# demoV1_0.net
KiCad netlist of a schematic drawn in Altium Designer
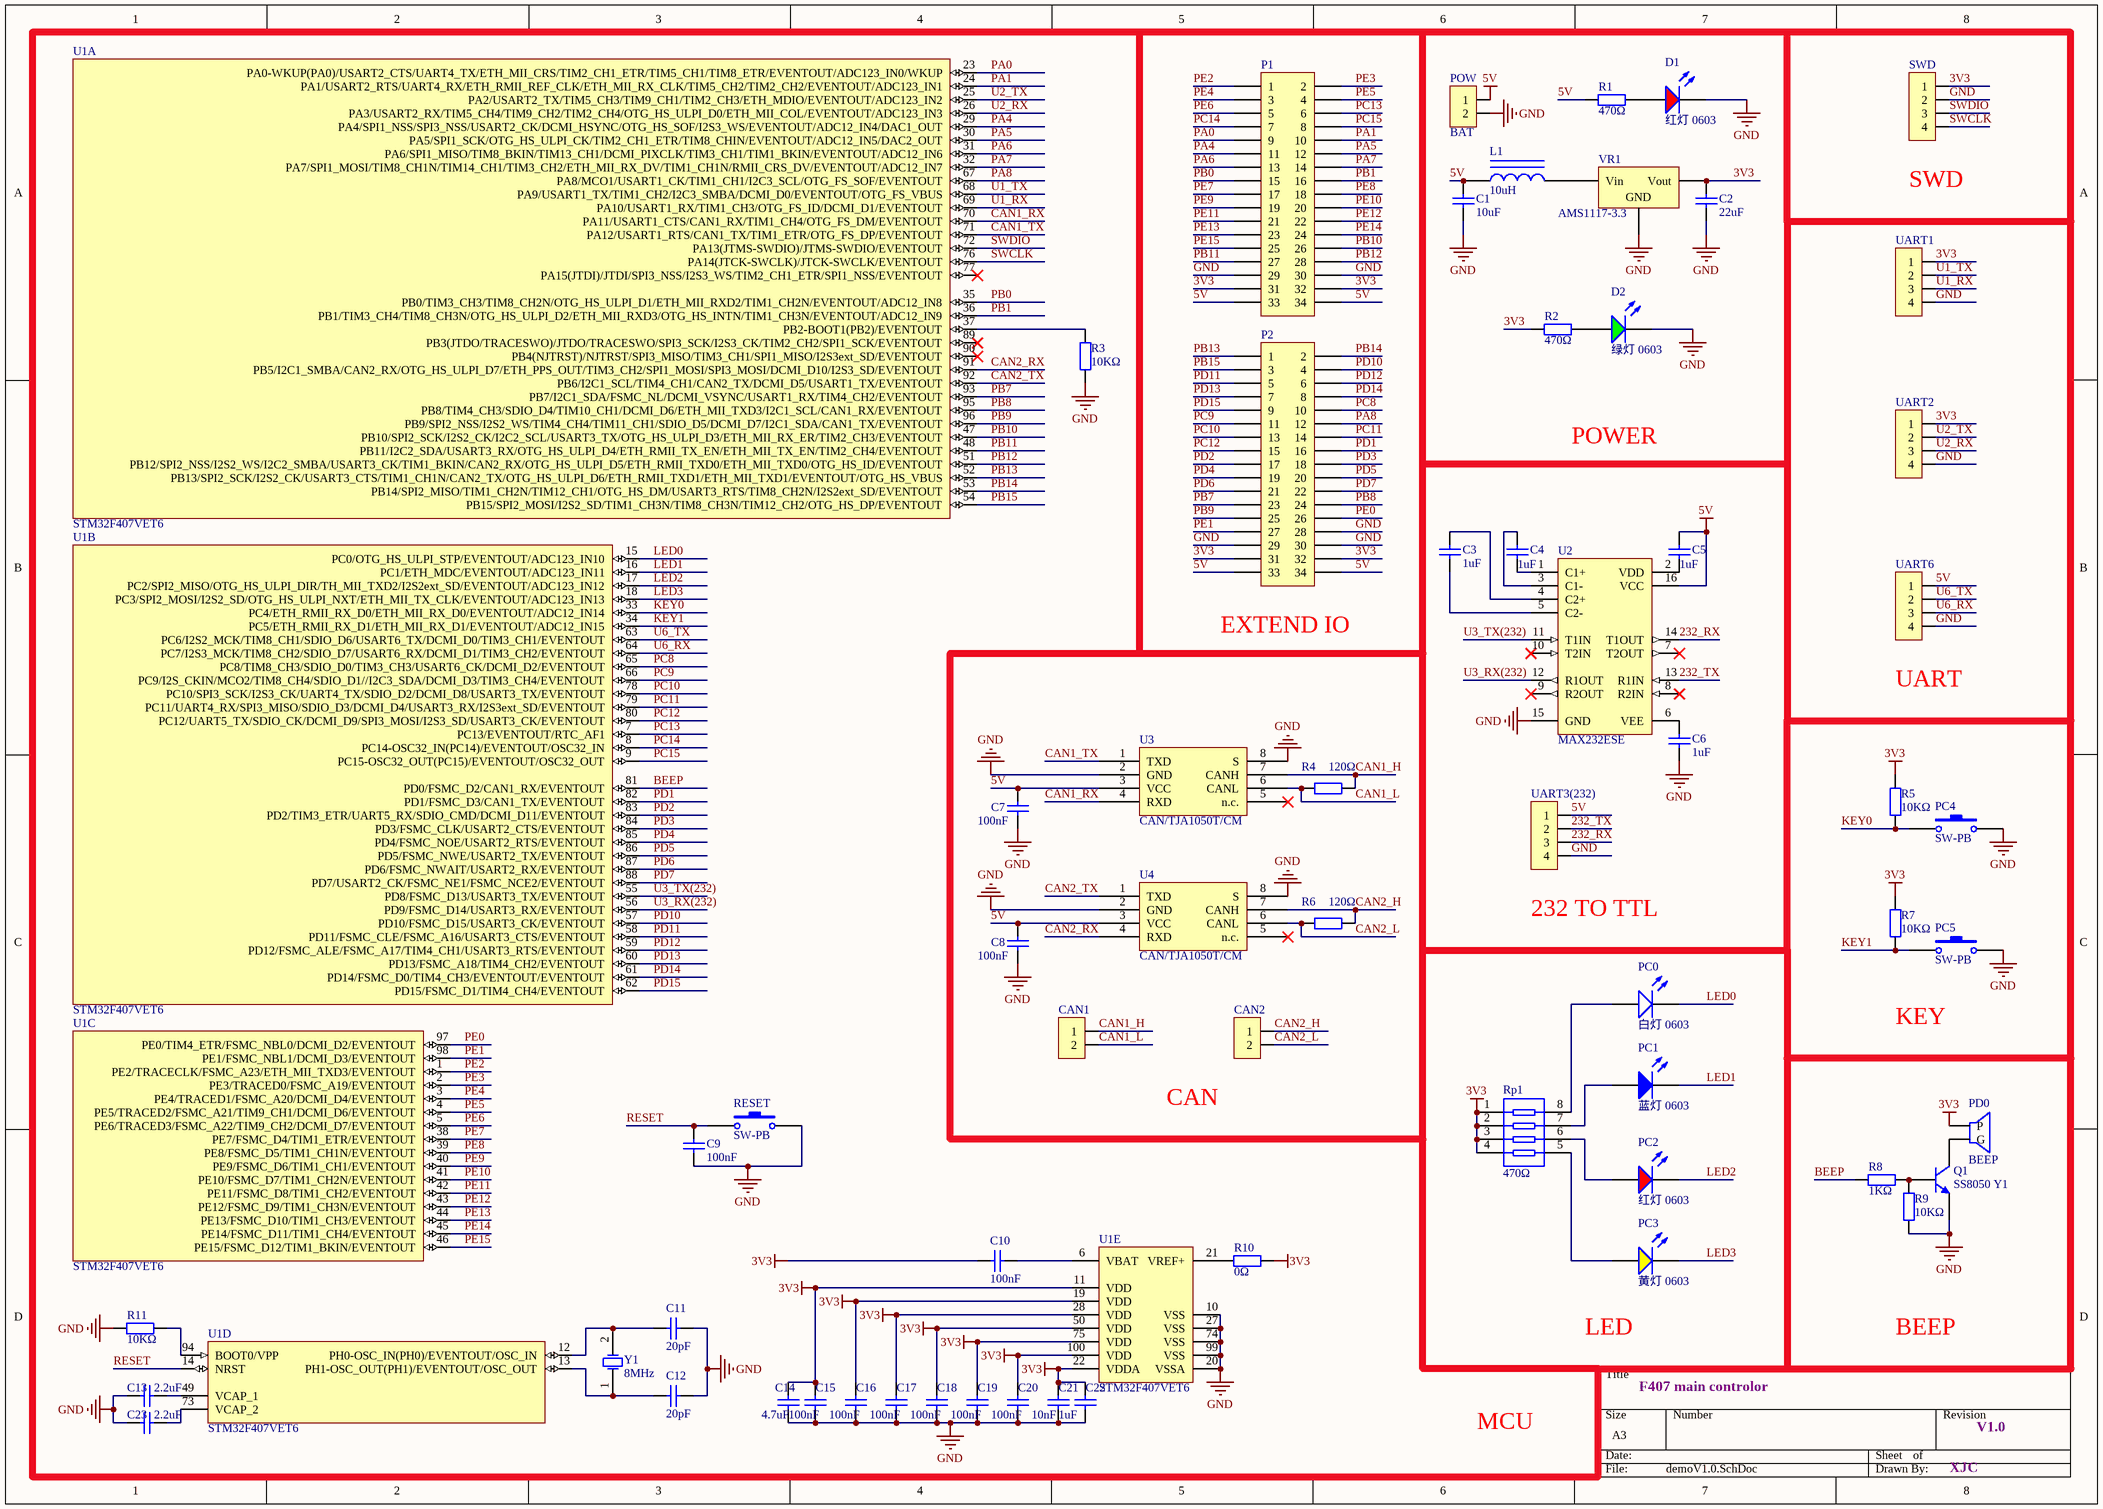
[diagram p0: demoV1.0.SchDoc]

(export (version "E")
  (design (tool "Eeschema 10.0.6"))
  (components
    (comp (ref "C1")
      (value "10uF")
      (footprint "0603_C")
      (description "贴片电容")
      (libsource (lib "Cap") (part "0603 10uF (106) 10% 10V"))
    )
    (comp (ref "C2")
      (value "22uF")
      (footprint "0603_C")
      (description "贴片电容")
      (libsource (lib "Cap") (part "0603 22uF (226) 20% 6.3V"))
    )
    (comp (ref "C3")
      (value "1uF")
      (footprint "0603_C")
      (description "贴片电容")
      (libsource (lib "Cap") (part "0603 1uF (105) 10% 50V"))
    )
    (comp (ref "C4")
      (value "1uF")
      (footprint "0603_C")
      (description "贴片电容")
      (libsource (lib "Cap") (part "0603 1uF (105) 10% 50V"))
    )
    (comp (ref "C5")
      (value "1uF")
      (footprint "0603_C")
      (description "贴片电容")
      (libsource (lib "Cap") (part "0603 1uF (105) 10% 50V"))
    )
    (comp (ref "C6")
      (value "1uF")
      (footprint "0603_C")
      (description "贴片电容")
      (libsource (lib "Cap") (part "0603 1uF (105) 10% 50V"))
    )
    (comp (ref "C7")
      (value "100nF")
      (footprint "0603_C")
      (description "贴片电容")
      (libsource (lib "Cap") (part "0603 100nF (104) 10% 50V"))
    )
    (comp (ref "C8")
      (value "100nF")
      (footprint "0603_C")
      (description "贴片电容")
      (libsource (lib "Cap") (part "0603 100nF (104) 10% 50V"))
    )
    (comp (ref "C9")
      (value "100nF")
      (footprint "0603_C")
      (description "贴片电容")
      (libsource (lib "Cap") (part "0603 100nF (104) 10% 50V"))
    )
    (comp (ref "C10")
      (value "100nF")
      (footprint "0603_C")
      (description "贴片电容")
      (libsource (lib "Cap") (part "0603 100nF (104) 10% 50V"))
    )
    (comp (ref "C11")
      (value "20pF")
      (footprint "0603_C")
      (description "贴片电容")
      (libsource (lib "Cap") (part "0603 20pF (200) 5% 50V"))
    )
    (comp (ref "C12")
      (value "20pF")
      (footprint "0603_C")
      (description "贴片电容")
      (libsource (lib "Cap") (part "0603 20pF (200) 5% 50V"))
    )
    (comp (ref "C13")
      (value "2.2uF")
      (footprint "0603_C")
      (description "贴片电容")
      (libsource (lib "Cap") (part "0603 2.2uF (225) 10% 16V"))
    )
    (comp (ref "C14")
      (value "4.7uF")
      (footprint "0603_C")
      (description "贴片电容")
      (libsource (lib "Cap") (part "0603 4.7uF (475) 10% 16V"))
    )
    (comp (ref "C15")
      (value "100nF")
      (footprint "0603_C")
      (description "贴片电容")
      (libsource (lib "Cap") (part "0603 100nF (104) 10% 50V"))
    )
    (comp (ref "C16")
      (value "100nF")
      (footprint "0603_C")
      (description "贴片电容")
      (libsource (lib "Cap") (part "0603 100nF (104) 10% 50V"))
    )
    (comp (ref "C17")
      (value "100nF")
      (footprint "0603_C")
      (description "贴片电容")
      (libsource (lib "Cap") (part "0603 100nF (104) 10% 50V"))
    )
    (comp (ref "C18")
      (value "100nF")
      (footprint "0603_C")
      (description "贴片电容")
      (libsource (lib "Cap") (part "0603 100nF (104) 10% 50V"))
    )
    (comp (ref "C19")
      (value "100nF")
      (footprint "0603_C")
      (description "贴片电容")
      (libsource (lib "Cap") (part "0603 100nF (104) 10% 50V"))
    )
    (comp (ref "C20")
      (value "100nF")
      (footprint "0603_C")
      (description "贴片电容")
      (libsource (lib "Cap") (part "0603 100nF (104) 10% 50V"))
    )
    (comp (ref "C21")
      (value "10nF")
      (footprint "0603_C")
      (description "贴片电容")
      (libsource (lib "Cap") (part "0603 10nF (103) 10% 50V"))
    )
    (comp (ref "C22")
      (value "1uF")
      (footprint "0603_C")
      (description "贴片电容")
      (libsource (lib "Cap") (part "0603 1uF (105) 10% 50V"))
    )
    (comp (ref "C23")
      (value "2.2uF")
      (footprint "0603_C")
      (description "贴片电容")
      (libsource (lib "Cap") (part "0603 2.2uF (225) 10% 16V"))
    )
    (comp (ref "CAN1")
      (value "CAN")
      (footprint "XH-2")
      (description "Connector")
      (libsource (lib "连接器件") (part "CON2"))
    )
    (comp (ref "CAN2")
      (value "CAN")
      (footprint "XH-2")
      (description "Connector")
      (libsource (lib "连接器件") (part "CON2"))
    )
    (comp (ref "D1")
      (value "红灯 0603")
      (footprint "0603_LED_S1")
      (description "发光二极管")
      (libsource (lib "LED") (part "0603 红灯"))
    )
    (comp (ref "D2")
      (value "绿灯 0603")
      (footprint "0603_LED_S1")
      (description "发光二极管")
      (libsource (lib "LED") (part "0603 绿灯"))
    )
    (comp (ref "L1")
      (value "10uH")
      (footprint "0603_L")
      (description "贴片电感")
      (libsource (lib "IUD") (part "0603 10uH 10%"))
    )
    (comp (ref "P1")
      (value "Header 17X2")
      (footprint "HDR2X17")
      (description "Header, 17-Pin, Dual row")
      (fields (field (name "PUBLISHER") "Altium Limited"))
      (libsource (lib "Miscellaneous Connectors") (part "Header 17X2"))
    )
    (comp (ref "P2")
      (value "Header 17X2")
      (footprint "HDR2X17")
      (description "Header, 17-Pin, Dual row")
      (fields (field (name "PUBLISHER") "Altium Limited"))
      (libsource (lib "Miscellaneous Connectors") (part "Header 17X2"))
    )
    (comp (ref "PC0")
      (value "白灯 0603")
      (footprint "0603_LED_S1")
      (description "发光二极管")
      (libsource (lib "LED") (part "0603 白灯"))
    )
    (comp (ref "PC1")
      (value "蓝灯 0603")
      (footprint "0603_LED_S1")
      (description "发光二极管")
      (libsource (lib "LED") (part "0603 蓝灯"))
    )
    (comp (ref "PC2")
      (value "红灯 0603")
      (footprint "0603_LED_S1")
      (description "发光二极管")
      (libsource (lib "LED") (part "0603 红灯"))
    )
    (comp (ref "PC3")
      (value "黄灯 0603")
      (footprint "0603_LED_S1")
      (description "发光二极管")
      (libsource (lib "LED") (part "0603 黄灯"))
    )
    (comp (ref "PC4")
      (value "SW-PB")
      (footprint "SW_PB2_A1")
      (description "微动开关")
      (fields (field (name "PUBLISHER") "Altium Limited"))
      (libsource (lib "Fszhang") (part "SW-PB"))
    )
    (comp (ref "PC5")
      (value "SW-PB")
      (footprint "SW_PB2_A1")
      (description "微动开关")
      (fields (field (name "PUBLISHER") "Altium Limited"))
      (libsource (lib "Fszhang") (part "SW-PB"))
    )
    (comp (ref "PD0")
      (value "BEEP")
      (footprint "BELL-5")
      (libsource (lib "Explorer STM32F407封装库") (part "BEEP"))
    )
    (comp (ref "POW")
      (value "BAT")
      (footprint "XH-2")
      (description "Connector")
      (libsource (lib "连接器件") (part "CON2"))
    )
    (comp (ref "Q1")
      (value "SS8050 Y1")
      (footprint "SOT-23(SOT-23-3)")
      (description "三极管")
      (libsource (lib "Transistor_NPN") (part "SOT-23 SS8050 Y1"))
    )
    (comp (ref "R1")
      (value "470Ω")
      (footprint "0603_R")
      (description "贴片电阻")
      (libsource (lib "RES") (part "0603 470Ω (4700) 1%"))
    )
    (comp (ref "R2")
      (value "470Ω")
      (footprint "0603_R")
      (description "贴片电阻")
      (libsource (lib "RES") (part "0603 470Ω (4700) 1%"))
    )
    (comp (ref "R3")
      (value "10KΩ")
      (footprint "0603_R")
      (description "贴片电阻")
      (libsource (lib "RES") (part "0603 10KΩ (1002) 1%"))
    )
    (comp (ref "R4")
      (value "120Ω")
      (footprint "0603_R")
      (description "贴片电阻")
      (libsource (lib "RES") (part "0603 120Ω (1200) 1%"))
    )
    (comp (ref "R5")
      (value "10KΩ")
      (footprint "0603_R")
      (description "贴片电阻")
      (libsource (lib "RES") (part "0603 10KΩ (1002) 1%"))
    )
    (comp (ref "R6")
      (value "120Ω")
      (footprint "0603_R")
      (description "贴片电阻")
      (libsource (lib "RES") (part "0603 120Ω (1200) 1%"))
    )
    (comp (ref "R7")
      (value "10KΩ")
      (footprint "0603_R")
      (description "贴片电阻")
      (libsource (lib "RES") (part "0603 10KΩ (1002) 1%"))
    )
    (comp (ref "R8")
      (value "1KΩ")
      (footprint "0603_R")
      (description "贴片电阻")
      (libsource (lib "RES") (part "0603 1KΩ (1001) 1%"))
    )
    (comp (ref "R9")
      (value "10KΩ")
      (footprint "0603_R")
      (description "贴片电阻")
      (libsource (lib "RES") (part "0603 10KΩ (1002) 1%"))
    )
    (comp (ref "R10")
      (value "0Ω")
      (footprint "0603_R")
      (description "贴片电阻")
      (libsource (lib "RES") (part "0603 0Ω (0R0) 1%"))
    )
    (comp (ref "R11")
      (value "10KΩ")
      (footprint "0603_R")
      (description "贴片电阻")
      (libsource (lib "") (part "0603 10KΩ (1002) 1%_1"))
    )
    (comp (ref "RESET")
      (value "SW-PB")
      (footprint "SW_PB2_A1")
      (description "微动开关")
      (fields (field (name "PUBLISHER") "Altium Limited"))
      (libsource (lib "Fszhang") (part "SW-PB"))
    )
    (comp (ref "Rp1")
      (value "470Ω")
      (footprint "0603_Rx4")
      (description "贴片排阻")
      (libsource (lib "RES") (part "0603*4 470Ω (471) 5%"))
    )
    (comp (ref "SWD")
      (value "SWD")
      (footprint "PH-4")
      (description "Connector")
      (libsource (lib "连接器件") (part "CON4"))
    )
    (comp (ref "U1")
      (value "STM32F407VET6")
      (footprint "LQFP-100_14x14x05P")
      (description "ARM")
      (libsource (lib "MCU") (part "STM32F407VET6"))
    )
    (comp (ref "U2")
      (value "MAX232ESE")
      (footprint "SOIC-16_150mil")
      (description "RS232")
      (libsource (lib "IC") (part "MAX232ESE_[C26860]"))
    )
    (comp (ref "U3")
      (value "CAN/TJA1050T/CM")
      (footprint "SOIC-8_150mil")
      (description "CAN")
      (libsource (lib "IC") (part "CAN/TJA1050T/CM_[C6952]"))
    )
    (comp (ref "U4")
      (value "CAN/TJA1050T/CM")
      (footprint "SOIC-8_150mil")
      (description "CAN")
      (libsource (lib "IC") (part "CAN/TJA1050T/CM_[C6952]"))
    )
    (comp (ref "UART1")
      (value "~")
      (footprint "XH-4")
      (description "Connector")
      (libsource (lib "连接器件") (part "CON4"))
    )
    (comp (ref "UART2")
      (value "~")
      (footprint "XH-4")
      (description "Connector")
      (libsource (lib "连接器件") (part "CON4"))
    )
    (comp (ref "UART3(232)")
      (value "~")
      (footprint "XH-4")
      (description "Connector")
      (libsource (lib "连接器件") (part "CON4"))
    )
    (comp (ref "UART6")
      (value "~")
      (footprint "XH-4")
      (description "Connector")
      (libsource (lib "连接器件") (part "CON4"))
    )
    (comp (ref "VR1")
      (value "AMS1117-3.3")
      (footprint "SOT-223")
      (description "低压差线性稳压(LDO)")
      (libsource (lib "LDO") (part "SOT-223 AMS1117-3.3"))
    )
    (comp (ref "Y1")
      (value "8MHz")
      (footprint "SMD-5032_2P")
      (description "贴片晶振")
      (libsource (lib "CrystalOscillator") (part "SMD-5032_2P 8MHz 20ppm 20pF"))
    )
  )
  (nets
    (net (code "1") (name "/232_RX") (class "Default")
      (node (ref "U2") (pin "14") (pinfunction "T1OUT_14") (pintype "output"))
      (node (ref "UART3(232)") (pin "3") (pinfunction "3_3") (pintype "passive"))
    )
    (net (code "2") (name "/232_TX") (class "Default")
      (node (ref "U2") (pin "13") (pinfunction "R1IN_13") (pintype "input"))
      (node (ref "UART3(232)") (pin "2") (pinfunction "2_2") (pintype "passive"))
    )
    (net (code "3") (name "/BEEP") (class "Default")
      (node (ref "R8") (pin "1") (pinfunction "1_1") (pintype "passive"))
      (node (ref "U1") (pin "81") (pinfunction "PD0/FSMC_D2/CAN1_RX/EVENTOUT_81") (pintype "bidirectional"))
    )
    (net (code "4") (name "/CAN1_H") (class "Default")
      (node (ref "CAN1") (pin "1") (pinfunction "1_1") (pintype "passive"))
      (node (ref "R4") (pin "2") (pinfunction "2_2") (pintype "passive"))
      (node (ref "U3") (pin "7") (pinfunction "CANH_7") (pintype "passive"))
    )
    (net (code "5") (name "/CAN1_L") (class "Default")
      (node (ref "CAN1") (pin "2") (pinfunction "2_2") (pintype "passive"))
      (node (ref "R4") (pin "1") (pinfunction "1_1") (pintype "passive"))
      (node (ref "U3") (pin "6") (pinfunction "CANL_6") (pintype "passive"))
    )
    (net (code "6") (name "/CAN1_RX") (class "Default")
      (node (ref "U1") (pin "70") (pinfunction "PA11/USART1_CTS/CAN1_RX/TIM1_CH4/OTG_FS_DM/EVENTOUT_70") (pintype "bidirectional"))
      (node (ref "U3") (pin "4") (pinfunction "RXD_4") (pintype "passive"))
    )
    (net (code "7") (name "/CAN1_TX") (class "Default")
      (node (ref "U1") (pin "71") (pinfunction "PA12/USART1_RTS/CAN1_TX/TIM1_ETR/OTG_FS_DP/EVENTOUT_71") (pintype "bidirectional"))
      (node (ref "U3") (pin "1") (pinfunction "TXD_1") (pintype "passive"))
    )
    (net (code "8") (name "/CAN2_H") (class "Default")
      (node (ref "CAN2") (pin "1") (pinfunction "1_1") (pintype "passive"))
      (node (ref "R6") (pin "2") (pinfunction "2_2") (pintype "passive"))
      (node (ref "U4") (pin "7") (pinfunction "CANH_7") (pintype "passive"))
    )
    (net (code "9") (name "/CAN2_L") (class "Default")
      (node (ref "CAN2") (pin "2") (pinfunction "2_2") (pintype "passive"))
      (node (ref "R6") (pin "1") (pinfunction "1_1") (pintype "passive"))
      (node (ref "U4") (pin "6") (pinfunction "CANL_6") (pintype "passive"))
    )
    (net (code "10") (name "/CAN2_RX") (class "Default")
      (node (ref "U1") (pin "91") (pinfunction "PB5/I2C1_SMBA/CAN2_RX/OTG_HS_ULPI_D7/ETH_PPS_OUT/TIM3_CH2/SPI1_MOSI/SPI3_MOSI/DCMI_D10/I2S3_SD/EVENTOUT_91") (pintype "bidirectional"))
      (node (ref "U4") (pin "4") (pinfunction "RXD_4") (pintype "passive"))
    )
    (net (code "11") (name "/CAN2_TX") (class "Default")
      (node (ref "U1") (pin "92") (pinfunction "PB6/I2C1_SCL/TIM4_CH1/CAN2_TX/DCMI_D5/USART1_TX/EVENTOUT_92") (pintype "bidirectional"))
      (node (ref "U4") (pin "1") (pinfunction "TXD_1") (pintype "passive"))
    )
    (net (code "12") (name "/KEY0") (class "Default")
      (node (ref "PC4") (pin "1") (pinfunction "1_1") (pintype "passive"))
      (node (ref "R5") (pin "1") (pinfunction "1_1") (pintype "passive"))
      (node (ref "U1") (pin "33") (pinfunction "PC4/ETH_RMII_RX_D0/ETH_MII_RX_D0/EVENTOUT/ADC12_IN14_33") (pintype "bidirectional"))
    )
    (net (code "13") (name "/KEY1") (class "Default")
      (node (ref "PC5") (pin "1") (pinfunction "1_1") (pintype "passive"))
      (node (ref "R7") (pin "1") (pinfunction "1_1") (pintype "passive"))
      (node (ref "U1") (pin "34") (pinfunction "PC5/ETH_RMII_RX_D1/ETH_MII_RX_D1/EVENTOUT/ADC12_IN15_34") (pintype "bidirectional"))
    )
    (net (code "14") (name "/LED0") (class "Default")
      (node (ref "PC0") (pin "K") (pinfunction "K_K") (pintype "passive"))
      (node (ref "U1") (pin "15") (pinfunction "PC0/OTG_HS_ULPI_STP/EVENTOUT/ADC123_IN10_15") (pintype "bidirectional"))
    )
    (net (code "15") (name "/LED1") (class "Default")
      (node (ref "PC1") (pin "K") (pinfunction "K_K") (pintype "passive"))
      (node (ref "U1") (pin "16") (pinfunction "PC1/ETH_MDC/EVENTOUT/ADC123_IN11_16") (pintype "bidirectional"))
    )
    (net (code "16") (name "/LED2") (class "Default")
      (node (ref "PC2") (pin "K") (pinfunction "K_K") (pintype "passive"))
      (node (ref "U1") (pin "17") (pinfunction "PC2/SPI2_MISO/OTG_HS_ULPI_DIR/TH_MII_TXD2/I2S2ext_SD/EVENTOUT/ADC123_IN12_17") (pintype "bidirectional"))
    )
    (net (code "17") (name "/LED3") (class "Default")
      (node (ref "PC3") (pin "K") (pinfunction "K_K") (pintype "passive"))
      (node (ref "U1") (pin "18") (pinfunction "PC3/SPI2_MOSI/I2S2_SD/OTG_HS_ULPI_NXT/ETH_MII_TX_CLK/EVENTOUT/ADC123_IN13_18") (pintype "bidirectional"))
    )
    (net (code "18") (name "/PA0") (class "Default")
      (node (ref "P1") (pin "9") (pinfunction "9_9") (pintype "passive"))
      (node (ref "U1") (pin "23") (pinfunction "PA0-WKUP(PA0)/USART2_CTS/UART4_TX/ETH_MII_CRS/TIM2_CH1_ETR/TIM5_CH1/TIM8_ETR/EVENTOUT/ADC123_IN0/WKUP_23") (pintype "bidirectional"))
    )
    (net (code "19") (name "/PA1") (class "Default")
      (node (ref "P1") (pin "10") (pinfunction "10_10") (pintype "passive"))
      (node (ref "U1") (pin "24") (pinfunction "PA1/USART2_RTS/UART4_RX/ETH_RMII_REF_CLK/ETH_MII_RX_CLK/TIM5_CH2/TIM2_CH2/EVENTOUT/ADC123_IN1_24") (pintype "bidirectional"))
    )
    (net (code "20") (name "/PA4") (class "Default")
      (node (ref "P1") (pin "11") (pinfunction "11_11") (pintype "passive"))
      (node (ref "U1") (pin "29") (pinfunction "PA4/SPI1_NSS/SPI3_NSS/USART2_CK/DCMI_HSYNC/OTG_HS_SOF/I2S3_WS/EVENTOUT/ADC12_IN4/DAC1_OUT_29") (pintype "bidirectional"))
    )
    (net (code "21") (name "/PA5") (class "Default")
      (node (ref "P1") (pin "12") (pinfunction "12_12") (pintype "passive"))
      (node (ref "U1") (pin "30") (pinfunction "PA5/SPI1_SCK/OTG_HS_ULPI_CK/TIM2_CH1_ETR/TIM8_CHIN/EVENTOUT/ADC12_IN5/DAC2_OUT_30") (pintype "bidirectional"))
    )
    (net (code "22") (name "/PA6") (class "Default")
      (node (ref "P1") (pin "13") (pinfunction "13_13") (pintype "passive"))
      (node (ref "U1") (pin "31") (pinfunction "PA6/SPI1_MISO/TIM8_BKIN/TIM13_CH1/DCMI_PIXCLK/TIM3_CH1/TIM1_BKIN/EVENTOUT/ADC12_IN6_31") (pintype "bidirectional"))
    )
    (net (code "23") (name "/PA7") (class "Default")
      (node (ref "P1") (pin "14") (pinfunction "14_14") (pintype "passive"))
      (node (ref "U1") (pin "32") (pinfunction "PA7/SPI1_MOSI/TIM8_CH1N/TIM14_CH1/TIM3_CH2/ETH_MII_RX_DV/TIM1_CH1N/RMII_CRS_DV/EVENTOUT/ADC12_IN7_32") (pintype "bidirectional"))
    )
    (net (code "24") (name "/PA8") (class "Default")
      (node (ref "P2") (pin "12") (pinfunction "12_12") (pintype "passive"))
      (node (ref "U1") (pin "67") (pinfunction "PA8/MCO1/USART1_CK/TIM1_CH1/I2C3_SCL/OTG_FS_SOF/EVENTOUT_67") (pintype "bidirectional"))
    )
    (net (code "25") (name "/PB0") (class "Default")
      (node (ref "P1") (pin "15") (pinfunction "15_15") (pintype "passive"))
      (node (ref "U1") (pin "35") (pinfunction "PB0/TIM3_CH3/TIM8_CH2N/OTG_HS_ULPI_D1/ETH_MII_RXD2/TIM1_CH2N/EVENTOUT/ADC12_IN8_35") (pintype "bidirectional"))
    )
    (net (code "26") (name "/PB1") (class "Default")
      (node (ref "P1") (pin "16") (pinfunction "16_16") (pintype "passive"))
      (node (ref "U1") (pin "36") (pinfunction "PB1/TIM3_CH4/TIM8_CH3N/OTG_HS_ULPI_D2/ETH_MII_RXD3/OTG_HS_INTN/TIM1_CH3N/EVENTOUT/ADC12_IN9_36") (pintype "bidirectional"))
    )
    (net (code "27") (name "/PB7") (class "Default")
      (node (ref "P2") (pin "23") (pinfunction "23_23") (pintype "passive"))
      (node (ref "U1") (pin "93") (pinfunction "PB7/I2C1_SDA/FSMC_NL/DCMI_VSYNC/USART1_RX/TIM4_CH2/EVENTOUT_93") (pintype "bidirectional"))
    )
    (net (code "28") (name "/PB8") (class "Default")
      (node (ref "P2") (pin "24") (pinfunction "24_24") (pintype "passive"))
      (node (ref "U1") (pin "95") (pinfunction "PB8/TIM4_CH3/SDIO_D4/TIM10_CH1/DCMI_D6/ETH_MII_TXD3/I2C1_SCL/CAN1_RX/EVENTOUT_95") (pintype "bidirectional"))
    )
    (net (code "29") (name "/PB9") (class "Default")
      (node (ref "P2") (pin "25") (pinfunction "25_25") (pintype "passive"))
      (node (ref "U1") (pin "96") (pinfunction "PB9/SPI2_NSS/I2S2_WS/TIM4_CH4/TIM11_CH1/SDIO_D5/DCMI_D7/I2C1_SDA/CAN1_TX/EVENTOUT_96") (pintype "bidirectional"))
    )
    (net (code "30") (name "/PB10") (class "Default")
      (node (ref "P1") (pin "26") (pinfunction "26_26") (pintype "passive"))
      (node (ref "U1") (pin "47") (pinfunction "PB10/SPI2_SCK/I2S2_CK/I2C2_SCL/USART3_TX/OTG_HS_ULPI_D3/ETH_MII_RX_ER/TIM2_CH3/EVENTOUT_47") (pintype "bidirectional"))
    )
    (net (code "31") (name "/PB11") (class "Default")
      (node (ref "P1") (pin "27") (pinfunction "27_27") (pintype "passive"))
      (node (ref "U1") (pin "48") (pinfunction "PB11/I2C2_SDA/USART3_RX/OTG_HS_ULPI_D4/ETH_RMII_TX_EN/ETH_MII_TX_EN/TIM2_CH4/EVENTOUT_48") (pintype "bidirectional"))
    )
    (net (code "32") (name "/PB12") (class "Default")
      (node (ref "P1") (pin "28") (pinfunction "28_28") (pintype "passive"))
      (node (ref "U1") (pin "51") (pinfunction "PB12/SPI2_NSS/I2S2_WS/I2C2_SMBA/USART3_CK/TIM1_BKIN/CAN2_RX/OTG_HS_ULPI_D5/ETH_RMII_TXD0/ETH_MII_TXD0/OTG_HS_ID/EVENTOUT_51") (pintype "bidirectional"))
    )
    (net (code "33") (name "/PB13") (class "Default")
      (node (ref "P2") (pin "1") (pinfunction "1_1") (pintype "passive"))
      (node (ref "U1") (pin "52") (pinfunction "PB13/SPI2_SCK/I2S2_CK/USART3_CTS/TIM1_CH1N/CAN2_TX/OTG_HS_ULPI_D6/ETH_RMII_TXD1/ETH_MII_TXD1/EVENTOUT/OTG_HS_VBUS_52") (pintype "bidirectional"))
    )
    (net (code "34") (name "/PB14") (class "Default")
      (node (ref "P2") (pin "2") (pinfunction "2_2") (pintype "passive"))
      (node (ref "U1") (pin "53") (pinfunction "PB14/SPI2_MISO/TIM1_CH2N/TIM12_CH1/OTG_HS_DM/USART3_RTS/TIM8_CH2N/I2S2ext_SD/EVENTOUT_53") (pintype "bidirectional"))
    )
    (net (code "35") (name "/PB15") (class "Default")
      (node (ref "P2") (pin "3") (pinfunction "3_3") (pintype "passive"))
      (node (ref "U1") (pin "54") (pinfunction "PB15/SPI2_MOSI/I2S2_SD/TIM1_CH3N/TIM8_CH3N/TIM12_CH2/OTG_HS_DP/EVENTOUT_54") (pintype "bidirectional"))
    )
    (net (code "36") (name "/PC8") (class "Default")
      (node (ref "P2") (pin "10") (pinfunction "10_10") (pintype "passive"))
      (node (ref "U1") (pin "65") (pinfunction "PC8/TIM8_CH3/SDIO_D0/TIM3_CH3/USART6_CK/DCMI_D2/EVENTOUT_65") (pintype "bidirectional"))
    )
    (net (code "37") (name "/PC9") (class "Default")
      (node (ref "P2") (pin "11") (pinfunction "11_11") (pintype "passive"))
      (node (ref "U1") (pin "66") (pinfunction "PC9/I2S_CKIN/MCO2/TIM8_CH4/SDIO_D1//I2C3_SDA/DCMI_D3/TIM3_CH4/EVENTOUT_66") (pintype "bidirectional"))
    )
    (net (code "38") (name "/PC10") (class "Default")
      (node (ref "P2") (pin "13") (pinfunction "13_13") (pintype "passive"))
      (node (ref "U1") (pin "78") (pinfunction "PC10/SPI3_SCK/I2S3_CK/UART4_TX/SDIO_D2/DCMI_D8/USART3_TX/EVENTOUT_78") (pintype "bidirectional"))
    )
    (net (code "39") (name "/PC11") (class "Default")
      (node (ref "P2") (pin "14") (pinfunction "14_14") (pintype "passive"))
      (node (ref "U1") (pin "79") (pinfunction "PC11/UART4_RX/SPI3_MISO/SDIO_D3/DCMI_D4/USART3_RX/I2S3ext_SD/EVENTOUT_79") (pintype "bidirectional"))
    )
    (net (code "40") (name "/PC12") (class "Default")
      (node (ref "P2") (pin "15") (pinfunction "15_15") (pintype "passive"))
      (node (ref "U1") (pin "80") (pinfunction "PC12/UART5_TX/SDIO_CK/DCMI_D9/SPI3_MOSI/I2S3_SD/USART3_CK/EVENTOUT_80") (pintype "bidirectional"))
    )
    (net (code "41") (name "/PC13") (class "Default")
      (node (ref "P1") (pin "6") (pinfunction "6_6") (pintype "passive"))
      (node (ref "U1") (pin "7") (pinfunction "PC13/EVENTOUT/RTC_AF1_7") (pintype "bidirectional"))
    )
    (net (code "42") (name "/PC14") (class "Default")
      (node (ref "P1") (pin "7") (pinfunction "7_7") (pintype "passive"))
      (node (ref "U1") (pin "8") (pinfunction "PC14-OSC32_IN(PC14)/EVENTOUT/OSC32_IN_8") (pintype "bidirectional"))
    )
    (net (code "43") (name "/PC15") (class "Default")
      (node (ref "P1") (pin "8") (pinfunction "8_8") (pintype "passive"))
      (node (ref "U1") (pin "9") (pinfunction "PC15-OSC32_OUT(PC15)/EVENTOUT/OSC32_OUT_9") (pintype "bidirectional"))
    )
    (net (code "44") (name "/PD1") (class "Default")
      (node (ref "P2") (pin "16") (pinfunction "16_16") (pintype "passive"))
      (node (ref "U1") (pin "82") (pinfunction "PD1/FSMC_D3/CAN1_TX/EVENTOUT_82") (pintype "bidirectional"))
    )
    (net (code "45") (name "/PD2") (class "Default")
      (node (ref "P2") (pin "17") (pinfunction "17_17") (pintype "passive"))
      (node (ref "U1") (pin "83") (pinfunction "PD2/TIM3_ETR/UART5_RX/SDIO_CMD/DCMI_D11/EVENTOUT_83") (pintype "bidirectional"))
    )
    (net (code "46") (name "/PD3") (class "Default")
      (node (ref "P2") (pin "18") (pinfunction "18_18") (pintype "passive"))
      (node (ref "U1") (pin "84") (pinfunction "PD3/FSMC_CLK/USART2_CTS/EVENTOUT_84") (pintype "bidirectional"))
    )
    (net (code "47") (name "/PD4") (class "Default")
      (node (ref "P2") (pin "19") (pinfunction "19_19") (pintype "passive"))
      (node (ref "U1") (pin "85") (pinfunction "PD4/FSMC_NOE/USART2_RTS/EVENTOUT_85") (pintype "bidirectional"))
    )
    (net (code "48") (name "/PD5") (class "Default")
      (node (ref "P2") (pin "20") (pinfunction "20_20") (pintype "passive"))
      (node (ref "U1") (pin "86") (pinfunction "PD5/FSMC_NWE/USART2_TX/EVENTOUT_86") (pintype "bidirectional"))
    )
    (net (code "49") (name "/PD6") (class "Default")
      (node (ref "P2") (pin "21") (pinfunction "21_21") (pintype "passive"))
      (node (ref "U1") (pin "87") (pinfunction "PD6/FSMC_NWAIT/USART2_RX/EVENTOUT_87") (pintype "bidirectional"))
    )
    (net (code "50") (name "/PD7") (class "Default")
      (node (ref "P2") (pin "22") (pinfunction "22_22") (pintype "passive"))
      (node (ref "U1") (pin "88") (pinfunction "PD7/USART2_CK/FSMC_NE1/FSMC_NCE2/EVENTOUT_88") (pintype "bidirectional"))
    )
    (net (code "51") (name "/PD10") (class "Default")
      (node (ref "P2") (pin "4") (pinfunction "4_4") (pintype "passive"))
      (node (ref "U1") (pin "57") (pinfunction "PD10/FSMC_D15/USART3_CK/EVENTOUT_57") (pintype "bidirectional"))
    )
    (net (code "52") (name "/PD11") (class "Default")
      (node (ref "P2") (pin "5") (pinfunction "5_5") (pintype "passive"))
      (node (ref "U1") (pin "58") (pinfunction "PD11/FSMC_CLE/FSMC_A16/USART3_CTS/EVENTOUT_58") (pintype "bidirectional"))
    )
    (net (code "53") (name "/PD12") (class "Default")
      (node (ref "P2") (pin "6") (pinfunction "6_6") (pintype "passive"))
      (node (ref "U1") (pin "59") (pinfunction "PD12/FSMC_ALE/FSMC_A17/TIM4_CH1/USART3_RTS/EVENTOUT_59") (pintype "bidirectional"))
    )
    (net (code "54") (name "/PD13") (class "Default")
      (node (ref "P2") (pin "7") (pinfunction "7_7") (pintype "passive"))
      (node (ref "U1") (pin "60") (pinfunction "PD13/FSMC_A18/TIM4_CH2/EVENTOUT_60") (pintype "bidirectional"))
    )
    (net (code "55") (name "/PD14") (class "Default")
      (node (ref "P2") (pin "8") (pinfunction "8_8") (pintype "passive"))
      (node (ref "U1") (pin "61") (pinfunction "PD14/FSMC_D0/TIM4_CH3/EVENTOUT/EVENTOUT_61") (pintype "bidirectional"))
    )
    (net (code "56") (name "/PD15") (class "Default")
      (node (ref "P2") (pin "9") (pinfunction "9_9") (pintype "passive"))
      (node (ref "U1") (pin "62") (pinfunction "PD15/FSMC_D1/TIM4_CH4/EVENTOUT_62") (pintype "bidirectional"))
    )
    (net (code "57") (name "/PE0") (class "Default")
      (node (ref "P2") (pin "26") (pinfunction "26_26") (pintype "passive"))
      (node (ref "U1") (pin "97") (pinfunction "PE0/TIM4_ETR/FSMC_NBL0/DCMI_D2/EVENTOUT_97") (pintype "bidirectional"))
    )
    (net (code "58") (name "/PE1") (class "Default")
      (node (ref "P2") (pin "27") (pinfunction "27_27") (pintype "passive"))
      (node (ref "U1") (pin "98") (pinfunction "PE1/FSMC_NBL1/DCMI_D3/EVENTOUT_98") (pintype "bidirectional"))
    )
    (net (code "59") (name "/PE2") (class "Default")
      (node (ref "P1") (pin "1") (pinfunction "1_1") (pintype "passive"))
      (node (ref "U1") (pin "1") (pinfunction "PE2/TRACECLK/FSMC_A23/ETH_MII_TXD3/EVENTOUT_1") (pintype "bidirectional"))
    )
    (net (code "60") (name "/PE3") (class "Default")
      (node (ref "P1") (pin "2") (pinfunction "2_2") (pintype "passive"))
      (node (ref "U1") (pin "2") (pinfunction "PE3/TRACED0/FSMC_A19/EVENTOUT_2") (pintype "bidirectional"))
    )
    (net (code "61") (name "/PE4") (class "Default")
      (node (ref "P1") (pin "3") (pinfunction "3_3") (pintype "passive"))
      (node (ref "U1") (pin "3") (pinfunction "PE4/TRACED1/FSMC_A20/DCMI_D4/EVENTOUT_3") (pintype "bidirectional"))
    )
    (net (code "62") (name "/PE5") (class "Default")
      (node (ref "P1") (pin "4") (pinfunction "4_4") (pintype "passive"))
      (node (ref "U1") (pin "4") (pinfunction "PE5/TRACED2/FSMC_A21/TIM9_CH1/DCMI_D6/EVENTOUT_4") (pintype "bidirectional"))
    )
    (net (code "63") (name "/PE6") (class "Default")
      (node (ref "P1") (pin "5") (pinfunction "5_5") (pintype "passive"))
      (node (ref "U1") (pin "5") (pinfunction "PE6/TRACED3/FSMC_A22/TIM9_CH2/DCMI_D7/EVENTOUT_5") (pintype "bidirectional"))
    )
    (net (code "64") (name "/PE7") (class "Default")
      (node (ref "P1") (pin "17") (pinfunction "17_17") (pintype "passive"))
      (node (ref "U1") (pin "38") (pinfunction "PE7/FSMC_D4/TIM1_ETR/EVENTOUT_38") (pintype "bidirectional"))
    )
    (net (code "65") (name "/PE8") (class "Default")
      (node (ref "P1") (pin "18") (pinfunction "18_18") (pintype "passive"))
      (node (ref "U1") (pin "39") (pinfunction "PE8/FSMC_D5/TIM1_CH1N/EVENTOUT_39") (pintype "bidirectional"))
    )
    (net (code "66") (name "/PE9") (class "Default")
      (node (ref "P1") (pin "19") (pinfunction "19_19") (pintype "passive"))
      (node (ref "U1") (pin "40") (pinfunction "PE9/FSMC_D6/TIM1_CH1/EVENTOUT_40") (pintype "bidirectional"))
    )
    (net (code "67") (name "/PE10") (class "Default")
      (node (ref "P1") (pin "20") (pinfunction "20_20") (pintype "passive"))
      (node (ref "U1") (pin "41") (pinfunction "PE10/FSMC_D7/TIM1_CH2N/EVENTOUT_41") (pintype "bidirectional"))
    )
    (net (code "68") (name "/PE11") (class "Default")
      (node (ref "P1") (pin "21") (pinfunction "21_21") (pintype "passive"))
      (node (ref "U1") (pin "42") (pinfunction "PE11/FSMC_D8/TIM1_CH2/EVENTOUT_42") (pintype "bidirectional"))
    )
    (net (code "69") (name "/PE12") (class "Default")
      (node (ref "P1") (pin "22") (pinfunction "22_22") (pintype "passive"))
      (node (ref "U1") (pin "43") (pinfunction "PE12/FSMC_D9/TIM1_CH3N/EVENTOUT_43") (pintype "bidirectional"))
    )
    (net (code "70") (name "/PE13") (class "Default")
      (node (ref "P1") (pin "23") (pinfunction "23_23") (pintype "passive"))
      (node (ref "U1") (pin "44") (pinfunction "PE13/FSMC_D10/TIM1_CH3/EVENTOUT_44") (pintype "bidirectional"))
    )
    (net (code "71") (name "/PE14") (class "Default")
      (node (ref "P1") (pin "24") (pinfunction "24_24") (pintype "passive"))
      (node (ref "U1") (pin "45") (pinfunction "PE14/FSMC_D11/TIM1_CH4/EVENTOUT_45") (pintype "bidirectional"))
    )
    (net (code "72") (name "/PE15") (class "Default")
      (node (ref "P1") (pin "25") (pinfunction "25_25") (pintype "passive"))
      (node (ref "U1") (pin "46") (pinfunction "PE15/FSMC_D12/TIM1_BKIN/EVENTOUT_46") (pintype "bidirectional"))
    )
    (net (code "73") (name "/RESET") (class "Default")
      (node (ref "C9") (pin "2") (pinfunction "2_2") (pintype "passive"))
      (node (ref "RESET") (pin "1") (pinfunction "1_1") (pintype "passive"))
      (node (ref "U1") (pin "14") (pinfunction "NRST_14") (pintype "bidirectional"))
    )
    (net (code "74") (name "/SWCLK") (class "Default")
      (node (ref "SWD") (pin "4") (pinfunction "4_4") (pintype "passive"))
      (node (ref "U1") (pin "76") (pinfunction "PA14(JTCK-SWCLK)/JTCK-SWCLK/EVENTOUT_76") (pintype "bidirectional"))
    )
    (net (code "75") (name "/SWDIO") (class "Default")
      (node (ref "SWD") (pin "3") (pinfunction "3_3") (pintype "passive"))
      (node (ref "U1") (pin "72") (pinfunction "PA13(JTMS-SWDIO)/JTMS-SWDIO/EVENTOUT_72") (pintype "bidirectional"))
    )
    (net (code "76") (name "/U1_RX") (class "Default")
      (node (ref "U1") (pin "69") (pinfunction "PA10/USART1_RX/TIM1_CH3/OTG_FS_ID/DCMI_D1/EVENTOUT_69") (pintype "bidirectional"))
      (node (ref "UART1") (pin "3") (pinfunction "3_3") (pintype "passive"))
    )
    (net (code "77") (name "/U1_TX") (class "Default")
      (node (ref "U1") (pin "68") (pinfunction "PA9/USART1_TX/TIM1_CH2/I2C3_SMBA/DCMI_D0/EVENTOUT/OTG_FS_VBUS_68") (pintype "bidirectional"))
      (node (ref "UART1") (pin "2") (pinfunction "2_2") (pintype "passive"))
    )
    (net (code "78") (name "/U2_RX") (class "Default")
      (node (ref "U1") (pin "26") (pinfunction "PA3/USART2_RX/TIM5_CH4/TIM9_CH2/TIM2_CH4/OTG_HS_ULPI_D0/ETH_MII_COL/EVENTOUT/ADC123_IN3_26") (pintype "bidirectional"))
      (node (ref "UART2") (pin "3") (pinfunction "3_3") (pintype "passive"))
    )
    (net (code "79") (name "/U2_TX") (class "Default")
      (node (ref "U1") (pin "25") (pinfunction "PA2/USART2_TX/TIM5_CH3/TIM9_CH1/TIM2_CH3/ETH_MDIO/EVENTOUT/ADC123_IN2_25") (pintype "bidirectional"))
      (node (ref "UART2") (pin "2") (pinfunction "2_2") (pintype "passive"))
    )
    (net (code "80") (name "/U3_RX(232)") (class "Default")
      (node (ref "U1") (pin "56") (pinfunction "PD9/FSMC_D14/USART3_RX/EVENTOUT_56") (pintype "bidirectional"))
      (node (ref "U2") (pin "12") (pinfunction "R1OUT_12") (pintype "output"))
    )
    (net (code "81") (name "/U3_TX(232)") (class "Default")
      (node (ref "U1") (pin "55") (pinfunction "PD8/FSMC_D13/USART3_TX/EVENTOUT_55") (pintype "bidirectional"))
      (node (ref "U2") (pin "11") (pinfunction "T1IN_11") (pintype "input"))
    )
    (net (code "82") (name "/U6_RX") (class "Default")
      (node (ref "U1") (pin "64") (pinfunction "PC7/I2S3_MCK/TIM8_CH2/SDIO_D7/USART6_RX/DCMI_D1/TIM3_CH2/EVENTOUT_64") (pintype "bidirectional"))
      (node (ref "UART6") (pin "3") (pinfunction "3_3") (pintype "passive"))
    )
    (net (code "83") (name "/U6_TX") (class "Default")
      (node (ref "U1") (pin "63") (pinfunction "PC6/I2S2_MCK/TIM8_CH1/SDIO_D6/USART6_TX/DCMI_D0/TIM3_CH1/EVENTOUT_63") (pintype "bidirectional"))
      (node (ref "UART6") (pin "2") (pinfunction "2_2") (pintype "passive"))
    )
    (net (code "84") (name "3V3") (class "Default")
      (node (ref "C10") (pin "1") (pinfunction "1_1") (pintype "passive"))
      (node (ref "C14") (pin "2") (pinfunction "2_2") (pintype "passive"))
      (node (ref "C15") (pin "2") (pinfunction "2_2") (pintype "passive"))
      (node (ref "C16") (pin "2") (pinfunction "2_2") (pintype "passive"))
      (node (ref "C17") (pin "2") (pinfunction "2_2") (pintype "passive"))
      (node (ref "C18") (pin "2") (pinfunction "2_2") (pintype "passive"))
      (node (ref "C19") (pin "2") (pinfunction "2_2") (pintype "passive"))
      (node (ref "C2") (pin "2") (pinfunction "2_2") (pintype "passive"))
      (node (ref "C20") (pin "2") (pinfunction "2_2") (pintype "passive"))
      (node (ref "C21") (pin "2") (pinfunction "2_2") (pintype "passive"))
      (node (ref "C22") (pin "2") (pinfunction "2_2") (pintype "passive"))
      (node (ref "P1") (pin "31") (pinfunction "31_31") (pintype "passive"))
      (node (ref "P1") (pin "32") (pinfunction "32_32") (pintype "passive"))
      (node (ref "P2") (pin "31") (pinfunction "31_31") (pintype "passive"))
      (node (ref "P2") (pin "32") (pinfunction "32_32") (pintype "passive"))
      (node (ref "PD0") (pin "1") (pinfunction "P_1") (pintype "passive"))
      (node (ref "R10") (pin "2") (pinfunction "2_2") (pintype "passive"))
      (node (ref "R2") (pin "1") (pinfunction "1_1") (pintype "passive"))
      (node (ref "R5") (pin "2") (pinfunction "2_2") (pintype "passive"))
      (node (ref "R7") (pin "2") (pinfunction "2_2") (pintype "passive"))
      (node (ref "Rp1") (pin "1") (pinfunction "1_1") (pintype "passive"))
      (node (ref "Rp1") (pin "2") (pinfunction "2_2") (pintype "passive"))
      (node (ref "Rp1") (pin "3") (pinfunction "3_3") (pintype "passive"))
      (node (ref "Rp1") (pin "4") (pinfunction "4_4") (pintype "passive"))
      (node (ref "SWD") (pin "1") (pinfunction "1_1") (pintype "passive"))
      (node (ref "U1") (pin "100") (pinfunction "VDD_100") (pintype "power_in"))
      (node (ref "U1") (pin "11") (pinfunction "VDD_11") (pintype "power_in"))
      (node (ref "U1") (pin "19") (pinfunction "VDD_19") (pintype "power_in"))
      (node (ref "U1") (pin "22") (pinfunction "VDDA_22") (pintype "power_in"))
      (node (ref "U1") (pin "28") (pinfunction "VDD_28") (pintype "power_in"))
      (node (ref "U1") (pin "50") (pinfunction "VDD_50") (pintype "power_in"))
      (node (ref "U1") (pin "75") (pinfunction "VDD_75") (pintype "power_in"))
      (node (ref "UART1") (pin "1") (pinfunction "1_1") (pintype "passive"))
      (node (ref "UART2") (pin "1") (pinfunction "1_1") (pintype "passive"))
      (node (ref "VR1") (pin "2") (pinfunction "Vout_2") (pintype "passive"))
    )
    (net (code "85") (name "5V") (class "Default")
      (node (ref "C1") (pin "2") (pinfunction "2_2") (pintype "passive"))
      (node (ref "C5") (pin "2") (pinfunction "2_2") (pintype "passive"))
      (node (ref "C7") (pin "2") (pinfunction "2_2") (pintype "passive"))
      (node (ref "C8") (pin "2") (pinfunction "2_2") (pintype "passive"))
      (node (ref "L1") (pin "1") (pinfunction "1_1") (pintype "passive"))
      (node (ref "P1") (pin "33") (pinfunction "33_33") (pintype "passive"))
      (node (ref "P1") (pin "34") (pinfunction "34_34") (pintype "passive"))
      (node (ref "P2") (pin "33") (pinfunction "33_33") (pintype "passive"))
      (node (ref "P2") (pin "34") (pinfunction "34_34") (pintype "passive"))
      (node (ref "POW") (pin "1") (pinfunction "1_1") (pintype "passive"))
      (node (ref "R1") (pin "1") (pinfunction "1_1") (pintype "passive"))
      (node (ref "U2") (pin "16") (pinfunction "VCC_16") (pintype "power_in"))
      (node (ref "U3") (pin "3") (pinfunction "VCC_3") (pintype "passive"))
      (node (ref "U4") (pin "3") (pinfunction "VCC_3") (pintype "passive"))
      (node (ref "UART3(232)") (pin "1") (pinfunction "1_1") (pintype "passive"))
      (node (ref "UART6") (pin "1") (pinfunction "1_1") (pintype "passive"))
    )
    (net (code "86") (name "GND") (class "Default")
      (node (ref "C1") (pin "1") (pinfunction "1_1") (pintype "passive"))
      (node (ref "C11") (pin "2") (pinfunction "2_2") (pintype "passive"))
      (node (ref "C12") (pin "2") (pinfunction "2_2") (pintype "passive"))
      (node (ref "C13") (pin "1") (pinfunction "1_1") (pintype "passive"))
      (node (ref "C14") (pin "1") (pinfunction "1_1") (pintype "passive"))
      (node (ref "C15") (pin "1") (pinfunction "1_1") (pintype "passive"))
      (node (ref "C16") (pin "1") (pinfunction "1_1") (pintype "passive"))
      (node (ref "C17") (pin "1") (pinfunction "1_1") (pintype "passive"))
      (node (ref "C18") (pin "1") (pinfunction "1_1") (pintype "passive"))
      (node (ref "C19") (pin "1") (pinfunction "1_1") (pintype "passive"))
      (node (ref "C2") (pin "1") (pinfunction "1_1") (pintype "passive"))
      (node (ref "C20") (pin "1") (pinfunction "1_1") (pintype "passive"))
      (node (ref "C21") (pin "1") (pinfunction "1_1") (pintype "passive"))
      (node (ref "C22") (pin "1") (pinfunction "1_1") (pintype "passive"))
      (node (ref "C23") (pin "1") (pinfunction "1_1") (pintype "passive"))
      (node (ref "C6") (pin "2") (pinfunction "2_2") (pintype "passive"))
      (node (ref "C7") (pin "1") (pinfunction "1_1") (pintype "passive"))
      (node (ref "C8") (pin "1") (pinfunction "1_1") (pintype "passive"))
      (node (ref "C9") (pin "1") (pinfunction "1_1") (pintype "passive"))
      (node (ref "D1") (pin "K") (pinfunction "K_K") (pintype "passive"))
      (node (ref "D2") (pin "K") (pinfunction "K_K") (pintype "passive"))
      (node (ref "P1") (pin "29") (pinfunction "29_29") (pintype "passive"))
      (node (ref "P1") (pin "30") (pinfunction "30_30") (pintype "passive"))
      (node (ref "P2") (pin "28") (pinfunction "28_28") (pintype "passive"))
      (node (ref "P2") (pin "29") (pinfunction "29_29") (pintype "passive"))
      (node (ref "P2") (pin "30") (pinfunction "30_30") (pintype "passive"))
      (node (ref "PC4") (pin "2") (pinfunction "2_2") (pintype "passive"))
      (node (ref "PC5") (pin "2") (pinfunction "2_2") (pintype "passive"))
      (node (ref "POW") (pin "2") (pinfunction "2_2") (pintype "passive"))
      (node (ref "Q1") (pin "2") (pinfunction "E_2") (pintype "passive"))
      (node (ref "R11") (pin "1") (pinfunction "1_1") (pintype "passive"))
      (node (ref "R3") (pin "1") (pinfunction "1_1") (pintype "passive"))
      (node (ref "R9") (pin "1") (pinfunction "1_1") (pintype "passive"))
      (node (ref "RESET") (pin "2") (pinfunction "2_2") (pintype "passive"))
      (node (ref "SWD") (pin "2") (pinfunction "2_2") (pintype "passive"))
      (node (ref "U1") (pin "10") (pinfunction "VSS_10") (pintype "power_in"))
      (node (ref "U1") (pin "20") (pinfunction "VSSA_20") (pintype "power_in"))
      (node (ref "U1") (pin "27") (pinfunction "VSS_27") (pintype "power_in"))
      (node (ref "U1") (pin "74") (pinfunction "VSS_74") (pintype "power_in"))
      (node (ref "U1") (pin "99") (pinfunction "VSS_99") (pintype "power_in"))
      (node (ref "U2") (pin "15") (pinfunction "GND_15") (pintype "power_in"))
      (node (ref "U3") (pin "2") (pinfunction "GND_2") (pintype "passive"))
      (node (ref "U3") (pin "8") (pinfunction "S_8") (pintype "passive"))
      (node (ref "U4") (pin "2") (pinfunction "GND_2") (pintype "passive"))
      (node (ref "U4") (pin "8") (pinfunction "S_8") (pintype "passive"))
      (node (ref "UART1") (pin "4") (pinfunction "4_4") (pintype "passive"))
      (node (ref "UART2") (pin "4") (pinfunction "4_4") (pintype "passive"))
      (node (ref "UART3(232)") (pin "4") (pinfunction "4_4") (pintype "passive"))
      (node (ref "UART6") (pin "4") (pinfunction "4_4") (pintype "passive"))
      (node (ref "VR1") (pin "1") (pinfunction "GND_1") (pintype "passive"))
    )
    (net (code "87") (name "Net-(D1-PadA)") (class "Default")
      (node (ref "D1") (pin "A") (pinfunction "A_A") (pintype "passive"))
      (node (ref "R1") (pin "2") (pinfunction "2_2") (pintype "passive"))
    )
    (net (code "88") (name "Net-(D2-PadA)") (class "Default")
      (node (ref "D2") (pin "A") (pinfunction "A_A") (pintype "passive"))
      (node (ref "R2") (pin "2") (pinfunction "2_2") (pintype "passive"))
    )
    (net (code "89") (name "Net-(PC0-PadA)") (class "Default")
      (node (ref "PC0") (pin "A") (pinfunction "A_A") (pintype "passive"))
      (node (ref "Rp1") (pin "8") (pinfunction "8_8") (pintype "passive"))
    )
    (net (code "90") (name "Net-(PC1-PadA)") (class "Default")
      (node (ref "PC1") (pin "A") (pinfunction "A_A") (pintype "passive"))
      (node (ref "Rp1") (pin "7") (pinfunction "7_7") (pintype "passive"))
    )
    (net (code "91") (name "Net-(PC2-PadA)") (class "Default")
      (node (ref "PC2") (pin "A") (pinfunction "A_A") (pintype "passive"))
      (node (ref "Rp1") (pin "6") (pinfunction "6_6") (pintype "passive"))
    )
    (net (code "92") (name "Net-(PC3-PadA)") (class "Default")
      (node (ref "PC3") (pin "A") (pinfunction "A_A") (pintype "passive"))
      (node (ref "Rp1") (pin "5") (pinfunction "5_5") (pintype "passive"))
    )
    (net (code "93") (name "Net-(PD0-G)") (class "Default")
      (node (ref "PD0") (pin "2") (pinfunction "G_2") (pintype "passive"))
      (node (ref "Q1") (pin "3") (pinfunction "C_3") (pintype "passive"))
    )
    (net (code "94") (name "Net-(Q1-B)") (class "Default")
      (node (ref "Q1") (pin "1") (pinfunction "B_1") (pintype "passive"))
      (node (ref "R8") (pin "2") (pinfunction "2_2") (pintype "passive"))
      (node (ref "R9") (pin "2") (pinfunction "2_2") (pintype "passive"))
    )
    (net (code "95") (name "Net-(U1A-PB2-BOOT1(PB2){slash}EVENTOUT)") (class "Default")
      (node (ref "R3") (pin "2") (pinfunction "2_2") (pintype "passive"))
      (node (ref "U1") (pin "37") (pinfunction "PB2-BOOT1(PB2)/EVENTOUT_37") (pintype "bidirectional"))
    )
    (net (code "96") (name "Net-(U1D-BOOT0{slash}VPP)") (class "Default")
      (node (ref "R11") (pin "2") (pinfunction "2_2") (pintype "passive"))
      (node (ref "U1") (pin "94") (pinfunction "BOOT0/VPP_94") (pintype "input"))
    )
    (net (code "97") (name "Net-(U1D-PH0-OSC_IN(PH0){slash}EVENTOUT{slash}OSC_IN)") (class "Default")
      (node (ref "C11") (pin "1") (pinfunction "1_1") (pintype "passive"))
      (node (ref "U1") (pin "12") (pinfunction "PH0-OSC_IN(PH0)/EVENTOUT/OSC_IN_12") (pintype "bidirectional"))
      (node (ref "Y1") (pin "2") (pinfunction "OSC2_2") (pintype "passive"))
    )
    (net (code "98") (name "Net-(U1D-PH1-OSC_OUT(PH1){slash}EVENTOUT{slash}OSC_OUT)") (class "Default")
      (node (ref "C12") (pin "1") (pinfunction "1_1") (pintype "passive"))
      (node (ref "U1") (pin "13") (pinfunction "PH1-OSC_OUT(PH1)/EVENTOUT/OSC_OUT_13") (pintype "bidirectional"))
      (node (ref "Y1") (pin "1") (pinfunction "OSC1_1") (pintype "passive"))
    )
    (net (code "99") (name "Net-(U1D-VCAP_1)") (class "Default")
      (node (ref "C13") (pin "2") (pinfunction "2_2") (pintype "passive"))
      (node (ref "U1") (pin "49") (pinfunction "VCAP_1_49") (pintype "power_in"))
    )
    (net (code "100") (name "Net-(U1D-VCAP_2)") (class "Default")
      (node (ref "C23") (pin "2") (pinfunction "2_2") (pintype "passive"))
      (node (ref "U1") (pin "73") (pinfunction "VCAP_2_73") (pintype "power_in"))
    )
    (net (code "101") (name "Net-(U1E-VBAT)") (class "Default")
      (node (ref "C10") (pin "2") (pinfunction "2_2") (pintype "passive"))
      (node (ref "U1") (pin "6") (pinfunction "VBAT_6") (pintype "power_in"))
    )
    (net (code "102") (name "Net-(U1E-VREF+)") (class "Default")
      (node (ref "R10") (pin "1") (pinfunction "1_1") (pintype "passive"))
      (node (ref "U1") (pin "21") (pinfunction "VREF+_21") (pintype "power_in"))
    )
    (net (code "103") (name "Net-(U2-C1+)") (class "Default")
      (node (ref "C4") (pin "1") (pinfunction "1_1") (pintype "passive"))
      (node (ref "U2") (pin "1") (pinfunction "C1+_1") (pintype "passive"))
    )
    (net (code "104") (name "Net-(U2-C1-)") (class "Default")
      (node (ref "C4") (pin "2") (pinfunction "2_2") (pintype "passive"))
      (node (ref "U2") (pin "3") (pinfunction "C1-_3") (pintype "passive"))
    )
    (net (code "105") (name "Net-(U2-C2+)") (class "Default")
      (node (ref "C3") (pin "2") (pinfunction "2_2") (pintype "passive"))
      (node (ref "U2") (pin "4") (pinfunction "C2+_4") (pintype "passive"))
    )
    (net (code "106") (name "Net-(U2-C2-)") (class "Default")
      (node (ref "C3") (pin "1") (pinfunction "1_1") (pintype "passive"))
      (node (ref "U2") (pin "5") (pinfunction "C2-_5") (pintype "passive"))
    )
    (net (code "107") (name "Net-(U2-VDD)") (class "Default")
      (node (ref "C5") (pin "1") (pinfunction "1_1") (pintype "passive"))
      (node (ref "U2") (pin "2") (pinfunction "VDD_2") (pintype "power_in"))
    )
    (net (code "108") (name "Net-(U2-VEE)") (class "Default")
      (node (ref "C6") (pin "1") (pinfunction "1_1") (pintype "passive"))
      (node (ref "U2") (pin "6") (pinfunction "VEE_6") (pintype "power_in"))
    )
    (net (code "109") (name "Net-(VR1-Vin)") (class "Default")
      (node (ref "L1") (pin "2") (pinfunction "2_2") (pintype "passive"))
      (node (ref "VR1") (pin "3") (pinfunction "Vin_3") (pintype "passive"))
    )
    (net (code "110") (name "unconnected-(U1A-PA15(JTDI){slash}JTDI{slash}SPI3_NSS{slash}I2S3_WS{slash}TIM2_CH1_ETR{slash}SPI1_NSS{slash}EVENTOUT-Pad77)") (class "Default")
      (node (ref "U1") (pin "77") (pinfunction "PA15(JTDI)/JTDI/SPI3_NSS/I2S3_WS/TIM2_CH1_ETR/SPI1_NSS/EVENTOUT_77") (pintype "bidirectional+no_connect"))
    )
    (net (code "111") (name "unconnected-(U1A-PB3(JTDO{slash}TRACESWO){slash}JTDO{slash}TRACESWO{slash}SPI3_SCK{slash}I2S3_CK{slash}TIM2_CH2{slash}SPI1_SCK{slash}EVENTOUT-Pad89)") (class "Default")
      (node (ref "U1") (pin "89") (pinfunction "PB3(JTDO/TRACESWO)/JTDO/TRACESWO/SPI3_SCK/I2S3_CK/TIM2_CH2/SPI1_SCK/EVENTOUT_89") (pintype "bidirectional+no_connect"))
    )
    (net (code "112") (name "unconnected-(U1A-PB4(NJTRST){slash}NJTRST{slash}SPI3_MISO{slash}TIM3_CH1{slash}SPI1_MISO{slash}I2S3ext_SD{slash}EVENTOUT-Pad90)") (class "Default")
      (node (ref "U1") (pin "90") (pinfunction "PB4(NJTRST)/NJTRST/SPI3_MISO/TIM3_CH1/SPI1_MISO/I2S3ext_SD/EVENTOUT_90") (pintype "bidirectional+no_connect"))
    )
    (net (code "113") (name "unconnected-(U2-R2IN-Pad8)") (class "Default")
      (node (ref "U2") (pin "8") (pinfunction "R2IN_8") (pintype "input+no_connect"))
    )
    (net (code "114") (name "unconnected-(U2-R2OUT-Pad9)") (class "Default")
      (node (ref "U2") (pin "9") (pinfunction "R2OUT_9") (pintype "output+no_connect"))
    )
    (net (code "115") (name "unconnected-(U2-T2IN-Pad10)") (class "Default")
      (node (ref "U2") (pin "10") (pinfunction "T2IN_10") (pintype "input+no_connect"))
    )
    (net (code "116") (name "unconnected-(U2-T2OUT-Pad7)") (class "Default")
      (node (ref "U2") (pin "7") (pinfunction "T2OUT_7") (pintype "output+no_connect"))
    )
    (net (code "117") (name "unconnected-(U3-n.c.-Pad5)") (class "Default")
      (node (ref "U3") (pin "5") (pinfunction "n.c._5") (pintype "passive+no_connect"))
    )
    (net (code "118") (name "unconnected-(U4-n.c.-Pad5)") (class "Default")
      (node (ref "U4") (pin "5") (pinfunction "n.c._5") (pintype "passive+no_connect"))
    )
  )
)
